# Standard_Chassis_v1_0.net
KiCad netlist of a schematic drawn in Altium Designer
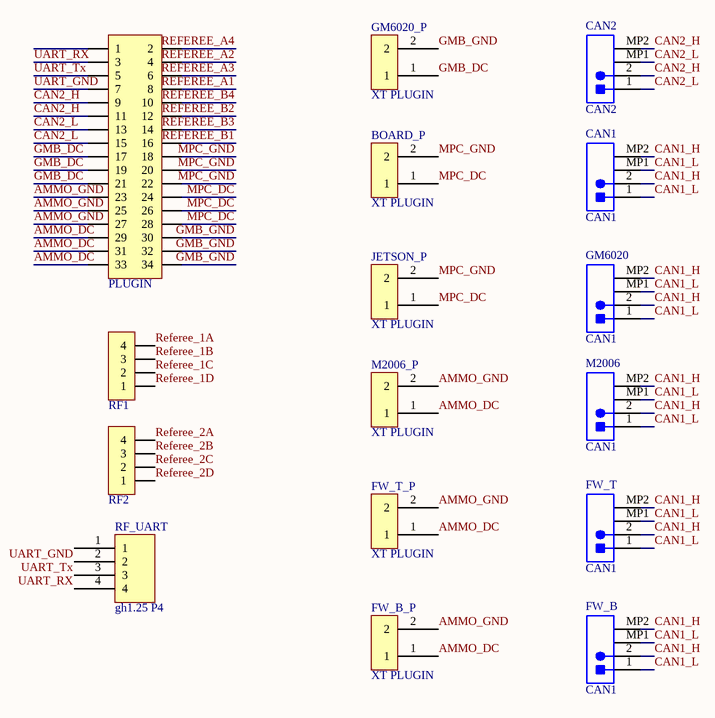
[diagram p0: Standard_Chassis_v1.0.SchDoc]

(export (version "E")
  (design (tool "Eeschema 10.0.6"))
  (components
    (comp (ref "BOARD_P")
      (value "XT PLUGIN")
      (footprint "XT30-M")
      (libsource (lib "schlib") (part "XT PLUGIN"))
    )
    (comp (ref "CAN1")
      (value "CAN1")
      (footprint "JST-BM02B-GHS-TBT_V")
      (fields (field (name "MANUFACTURER") "JST-Sales-America-Inc."))
      (libsource (lib "Altium Content Vault") (part "CN-1P-2M-R2"))
    )
    (comp (ref "CAN2")
      (value "CAN2")
      (footprint "JST-BM02B-GHS-TBT_V")
      (fields (field (name "MANUFACTURER") "JST-Sales-America-Inc."))
      (libsource (lib "Altium Content Vault") (part "CN-1P-2M-R2"))
    )
    (comp (ref "FW_B")
      (value "CAN1")
      (footprint "JST-BM02B-GHS-TBT_V")
      (fields (field (name "MANUFACTURER") "JST-Sales-America-Inc."))
      (libsource (lib "Altium Content Vault") (part "CN-1P-2M-R2"))
    )
    (comp (ref "FW_B_P")
      (value "XT PLUGIN")
      (footprint "XT30-M")
      (libsource (lib "schlib") (part "XT PLUGIN"))
    )
    (comp (ref "FW_T")
      (value "CAN1")
      (footprint "JST-BM02B-GHS-TBT_V")
      (fields (field (name "MANUFACTURER") "JST-Sales-America-Inc."))
      (libsource (lib "Altium Content Vault") (part "CN-1P-2M-R2"))
    )
    (comp (ref "FW_T_P")
      (value "XT PLUGIN")
      (footprint "XT30-M")
      (libsource (lib "schlib") (part "XT PLUGIN"))
    )
    (comp (ref "GM6020")
      (value "CAN1")
      (footprint "JST-BM02B-GHS-TBT_V")
      (fields (field (name "MANUFACTURER") "JST-Sales-America-Inc."))
      (libsource (lib "Altium Content Vault") (part "CN-1P-2M-R2"))
    )
    (comp (ref "GM6020_P")
      (value "XT PLUGIN")
      (footprint "XT30-M")
      (libsource (lib "schlib") (part "XT PLUGIN"))
    )
    (comp (ref "JETSON_P")
      (value "XT PLUGIN")
      (footprint "XT30-M")
      (libsource (lib "schlib") (part "XT PLUGIN"))
    )
    (comp (ref "M2006")
      (value "CAN1")
      (footprint "JST-BM02B-GHS-TBT_V")
      (fields (field (name "MANUFACTURER") "JST-Sales-America-Inc."))
      (libsource (lib "Altium Content Vault") (part "CN-1P-2M-R2"))
    )
    (comp (ref "M2006_P")
      (value "XT PLUGIN")
      (footprint "XT30-M")
      (libsource (lib "schlib") (part "XT PLUGIN"))
    )
    (comp (ref "PLUGIN")
      (value "Header 2X11")
      (footprint "IDC2.54-LI-2x17P")
      (description "17*2P接插件")
      (fields (field (name "版权归属") "封装库来自淘宝 ID：黄晶宝石"))
      (libsource (lib "5.4 - 接插件-脚距2.54 (100mil) ") (part "Header 17X2"))
    )
    (comp (ref "RF1")
      (value "HDR-1X4")
      (footprint "KF2510-LI-4P")
      (description "4P接插件")
      (fields (field (name "版权归属") "封装库来自淘宝 ID：黄晶宝石"))
      (libsource (lib "5.4 - 接插件-脚距2.54 (100mil) ") (part "Header 4"))
    )
    (comp (ref "RF2")
      (value "HDR-1X4")
      (footprint "KF2510-LI-4P")
      (description "4P接插件")
      (fields (field (name "版权归属") "封装库来自淘宝 ID：黄晶宝石"))
      (libsource (lib "5.4 - 接插件-脚距2.54 (100mil) ") (part "Header 4"))
    )
    (comp (ref "RF_UART")
      (value "gh1.25 P4")
      (footprint "GH1.25-4PIN")
      (libsource (lib "schlib") (part "gh1.25 P4"))
    )
  )
  (nets
    (net (code "1") (name "/AMMO_DC") (class "Default")
      (node (ref "FW_B_P") (pin "1") (pinfunction "1_1") (pintype "passive"))
      (node (ref "FW_T_P") (pin "1") (pinfunction "1_1") (pintype "passive"))
      (node (ref "M2006_P") (pin "1") (pinfunction "1_1") (pintype "passive"))
      (node (ref "PLUGIN") (pin "29") (pinfunction "29_29") (pintype "passive"))
      (node (ref "PLUGIN") (pin "31") (pinfunction "31_31") (pintype "passive"))
      (node (ref "PLUGIN") (pin "33") (pinfunction "33_33") (pintype "passive"))
    )
    (net (code "2") (name "/AMMO_GND") (class "Default")
      (node (ref "FW_B_P") (pin "2") (pinfunction "2_2") (pintype "passive"))
      (node (ref "FW_T_P") (pin "2") (pinfunction "2_2") (pintype "passive"))
      (node (ref "M2006_P") (pin "2") (pinfunction "2_2") (pintype "passive"))
      (node (ref "PLUGIN") (pin "23") (pinfunction "23_23") (pintype "passive"))
      (node (ref "PLUGIN") (pin "25") (pinfunction "25_25") (pintype "passive"))
      (node (ref "PLUGIN") (pin "27") (pinfunction "27_27") (pintype "passive"))
    )
    (net (code "3") (name "/CAN1_H") (class "Default")
      (node (ref "CAN1") (pin "2") (pinfunction "2_2") (pintype "passive"))
      (node (ref "CAN1") (pin "MP2") (pinfunction "MP2_MP2") (pintype "passive"))
      (node (ref "FW_B") (pin "2") (pinfunction "2_2") (pintype "passive"))
      (node (ref "FW_B") (pin "MP2") (pinfunction "MP2_MP2") (pintype "passive"))
      (node (ref "FW_T") (pin "2") (pinfunction "2_2") (pintype "passive"))
      (node (ref "FW_T") (pin "MP2") (pinfunction "MP2_MP2") (pintype "passive"))
      (node (ref "GM6020") (pin "2") (pinfunction "2_2") (pintype "passive"))
      (node (ref "GM6020") (pin "MP2") (pinfunction "MP2_MP2") (pintype "passive"))
      (node (ref "M2006") (pin "2") (pinfunction "2_2") (pintype "passive"))
      (node (ref "M2006") (pin "MP2") (pinfunction "MP2_MP2") (pintype "passive"))
    )
    (net (code "4") (name "/CAN1_L") (class "Default")
      (node (ref "CAN1") (pin "1") (pinfunction "1_1") (pintype "passive"))
      (node (ref "CAN1") (pin "MP1") (pinfunction "MP1_MP1") (pintype "passive"))
      (node (ref "FW_B") (pin "1") (pinfunction "1_1") (pintype "passive"))
      (node (ref "FW_B") (pin "MP1") (pinfunction "MP1_MP1") (pintype "passive"))
      (node (ref "FW_T") (pin "1") (pinfunction "1_1") (pintype "passive"))
      (node (ref "FW_T") (pin "MP1") (pinfunction "MP1_MP1") (pintype "passive"))
      (node (ref "GM6020") (pin "1") (pinfunction "1_1") (pintype "passive"))
      (node (ref "GM6020") (pin "MP1") (pinfunction "MP1_MP1") (pintype "passive"))
      (node (ref "M2006") (pin "1") (pinfunction "1_1") (pintype "passive"))
      (node (ref "M2006") (pin "MP1") (pinfunction "MP1_MP1") (pintype "passive"))
    )
    (net (code "5") (name "/CAN2_H") (class "Default")
      (node (ref "CAN2") (pin "2") (pinfunction "2_2") (pintype "passive"))
      (node (ref "CAN2") (pin "MP2") (pinfunction "MP2_MP2") (pintype "passive"))
      (node (ref "PLUGIN") (pin "11") (pinfunction "11_11") (pintype "passive"))
      (node (ref "PLUGIN") (pin "9") (pinfunction "9_9") (pintype "passive"))
    )
    (net (code "6") (name "/CAN2_L") (class "Default")
      (node (ref "CAN2") (pin "1") (pinfunction "1_1") (pintype "passive"))
      (node (ref "CAN2") (pin "MP1") (pinfunction "MP1_MP1") (pintype "passive"))
      (node (ref "PLUGIN") (pin "13") (pinfunction "13_13") (pintype "passive"))
      (node (ref "PLUGIN") (pin "15") (pinfunction "15_15") (pintype "passive"))
    )
    (net (code "7") (name "/GMB_DC") (class "Default")
      (node (ref "GM6020_P") (pin "1") (pinfunction "1_1") (pintype "passive"))
      (node (ref "PLUGIN") (pin "17") (pinfunction "17_17") (pintype "passive"))
      (node (ref "PLUGIN") (pin "19") (pinfunction "19_19") (pintype "passive"))
      (node (ref "PLUGIN") (pin "21") (pinfunction "21_21") (pintype "passive"))
    )
    (net (code "8") (name "/GMB_GND") (class "Default")
      (node (ref "GM6020_P") (pin "2") (pinfunction "2_2") (pintype "passive"))
      (node (ref "PLUGIN") (pin "30") (pinfunction "30_30") (pintype "passive"))
      (node (ref "PLUGIN") (pin "32") (pinfunction "32_32") (pintype "passive"))
      (node (ref "PLUGIN") (pin "34") (pinfunction "34_34") (pintype "passive"))
    )
    (net (code "9") (name "/MPC_DC") (class "Default")
      (node (ref "BOARD_P") (pin "1") (pinfunction "1_1") (pintype "passive"))
      (node (ref "JETSON_P") (pin "1") (pinfunction "1_1") (pintype "passive"))
      (node (ref "PLUGIN") (pin "24") (pinfunction "24_24") (pintype "passive"))
      (node (ref "PLUGIN") (pin "26") (pinfunction "26_26") (pintype "passive"))
      (node (ref "PLUGIN") (pin "28") (pinfunction "28_28") (pintype "passive"))
    )
    (net (code "10") (name "/MPC_GND") (class "Default")
      (node (ref "BOARD_P") (pin "2") (pinfunction "2_2") (pintype "passive"))
      (node (ref "JETSON_P") (pin "2") (pinfunction "2_2") (pintype "passive"))
      (node (ref "PLUGIN") (pin "18") (pinfunction "18_18") (pintype "passive"))
      (node (ref "PLUGIN") (pin "20") (pinfunction "20_20") (pintype "passive"))
      (node (ref "PLUGIN") (pin "22") (pinfunction "22_22") (pintype "passive"))
    )
    (net (code "11") (name "/REFEREE_A1") (class "Default")
      (node (ref "PLUGIN") (pin "8") (pinfunction "8_8") (pintype "passive"))
    )
    (net (code "12") (name "/REFEREE_A2") (class "Default")
      (node (ref "PLUGIN") (pin "4") (pinfunction "4_4") (pintype "passive"))
    )
    (net (code "13") (name "/REFEREE_A3") (class "Default")
      (node (ref "PLUGIN") (pin "6") (pinfunction "6_6") (pintype "passive"))
    )
    (net (code "14") (name "/REFEREE_A4") (class "Default")
      (node (ref "PLUGIN") (pin "2") (pinfunction "2_2") (pintype "passive"))
    )
    (net (code "15") (name "/REFEREE_B1") (class "Default")
      (node (ref "PLUGIN") (pin "16") (pinfunction "16_16") (pintype "passive"))
    )
    (net (code "16") (name "/REFEREE_B2") (class "Default")
      (node (ref "PLUGIN") (pin "12") (pinfunction "12_12") (pintype "passive"))
    )
    (net (code "17") (name "/REFEREE_B3") (class "Default")
      (node (ref "PLUGIN") (pin "14") (pinfunction "14_14") (pintype "passive"))
    )
    (net (code "18") (name "/REFEREE_B4") (class "Default")
      (node (ref "PLUGIN") (pin "10") (pinfunction "10_10") (pintype "passive"))
    )
    (net (code "19") (name "/Referee_1A") (class "Default")
      (node (ref "RF1") (pin "4") (pinfunction "4_4") (pintype "passive"))
    )
    (net (code "20") (name "/Referee_1B") (class "Default")
      (node (ref "RF1") (pin "3") (pinfunction "3_3") (pintype "passive"))
    )
    (net (code "21") (name "/Referee_1C") (class "Default")
      (node (ref "RF1") (pin "2") (pinfunction "2_2") (pintype "passive"))
    )
    (net (code "22") (name "/Referee_1D") (class "Default")
      (node (ref "RF1") (pin "1") (pinfunction "1_1") (pintype "passive"))
    )
    (net (code "23") (name "/Referee_2A") (class "Default")
      (node (ref "RF2") (pin "4") (pinfunction "4_4") (pintype "passive"))
    )
    (net (code "24") (name "/Referee_2B") (class "Default")
      (node (ref "RF2") (pin "3") (pinfunction "3_3") (pintype "passive"))
    )
    (net (code "25") (name "/Referee_2C") (class "Default")
      (node (ref "RF2") (pin "2") (pinfunction "2_2") (pintype "passive"))
    )
    (net (code "26") (name "/Referee_2D") (class "Default")
      (node (ref "RF2") (pin "1") (pinfunction "1_1") (pintype "passive"))
    )
    (net (code "27") (name "/UART_GND") (class "Default")
      (node (ref "PLUGIN") (pin "7") (pinfunction "7_7") (pintype "passive"))
      (node (ref "RF_UART") (pin "2") (pinfunction "2_2") (pintype "passive"))
    )
    (net (code "28") (name "/UART_RX") (class "Default")
      (node (ref "PLUGIN") (pin "3") (pinfunction "3_3") (pintype "passive"))
      (node (ref "RF_UART") (pin "4") (pinfunction "4_4") (pintype "passive"))
    )
    (net (code "29") (name "/UART_Tx") (class "Default")
      (node (ref "PLUGIN") (pin "5") (pinfunction "5_5") (pintype "passive"))
      (node (ref "RF_UART") (pin "3") (pinfunction "3_3") (pintype "passive"))
    )
    (net (code "30") (name "unconnected-(PLUGIN-Pad1)") (class "Default")
      (node (ref "PLUGIN") (pin "1") (pinfunction "1_1") (pintype "passive"))
    )
    (net (code "31") (name "unconnected-(RF_UART-Pad1)") (class "Default")
      (node (ref "RF_UART") (pin "1") (pinfunction "1_1") (pintype "passive"))
    )
  )
)
